# NNP-DWG-165-001-000_BP2_System_Pg_2_of_6.net
KiCad netlist of a schematic drawn in Altium Designer
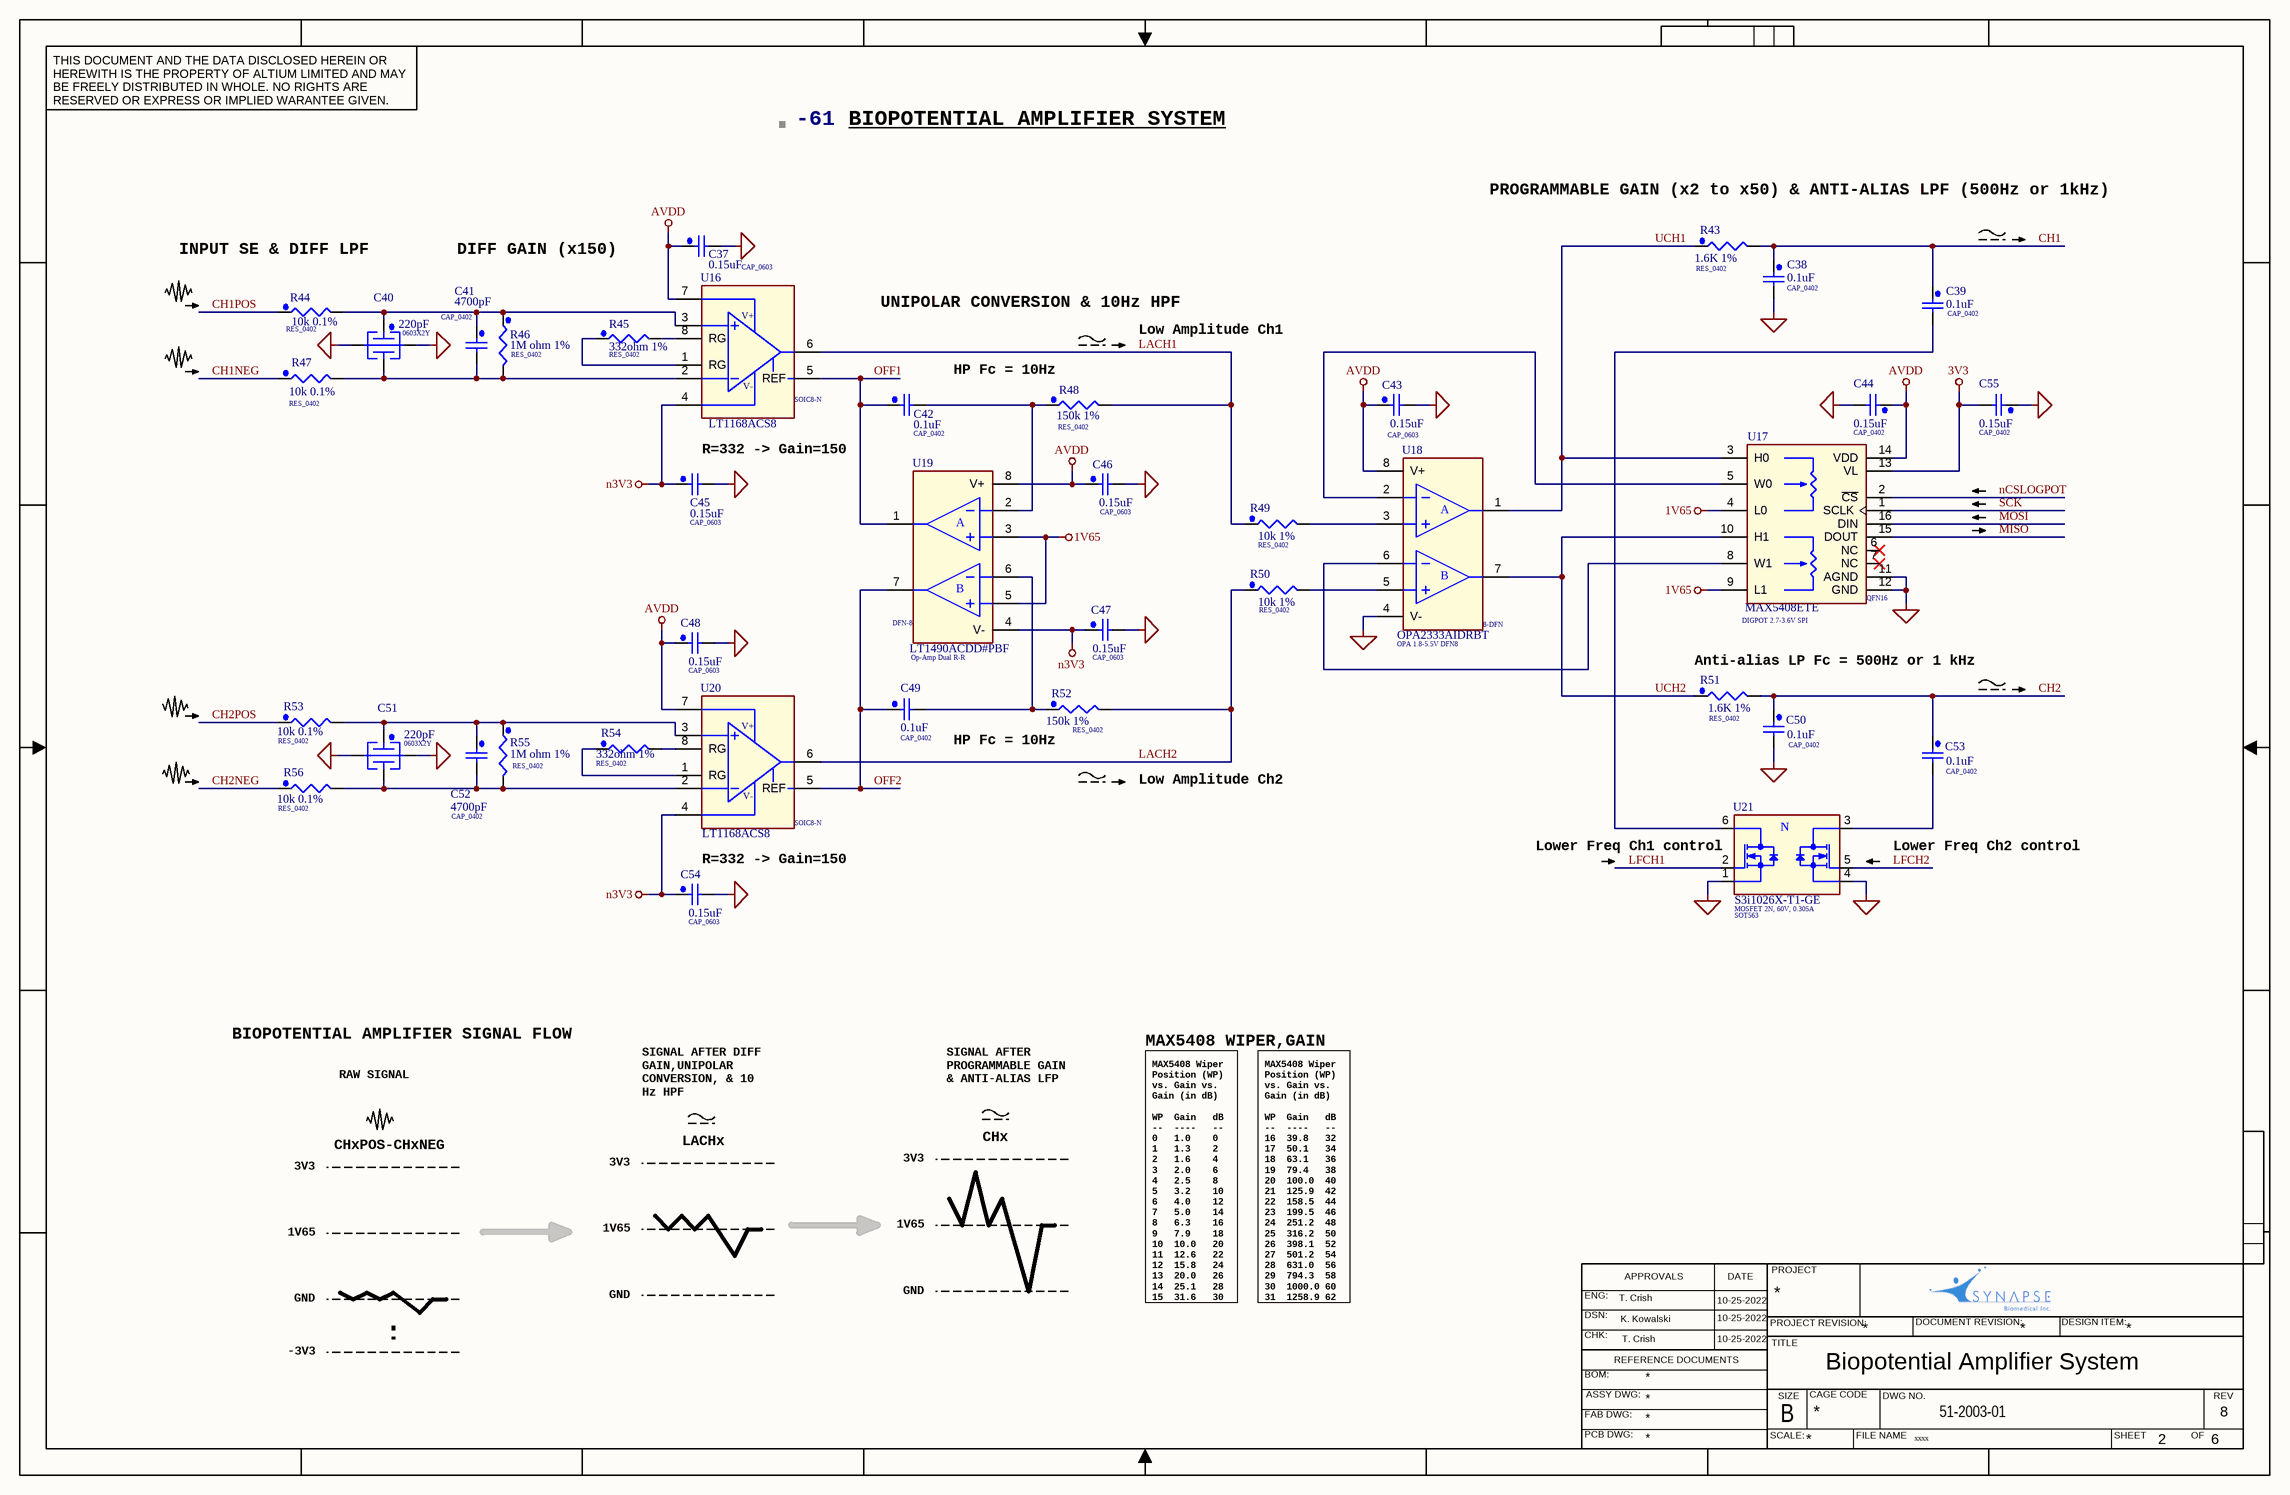
[diagram p0: NNP-DWG-165-001-000 BP2 System Pg 2 of 6.SchDoc]

(export (version "E")
  (design (tool "Eeschema 10.0.6"))
  (components
    (comp (ref "-61")
      (value "BOM_S1")
      (description "BOM item small graphic")
      (fields (field (name "XDESCRIPTION") "BIOPOTENTIAL AMPLIFIER SYSTEM"))
      (libsource (lib "BOM_sym") (part "BOM_S1"))
    )
    (comp (ref "C37")
      (value "0.15uF")
      (footprint "CAP_0603")
      (description "0.15uF, 16V, X7R, 10%, 0603, RoHS")
      (fields
        (field (name "MFR") "Samsung Corp")
        (field (name "PACKAGEDESCRIPTION") "CAP_0603")
        (field (name "MPN") "CL05B154KO5NNNC")
      )
      (libsource (lib "NNPS Integrated Parts") (part "GRM188R71C154KA01D"))
    )
    (comp (ref "C38")
      (value "0.1uF")
      (footprint "CAP_0402")
      (description "0.1uF, 16V, X7R, 0402, RoHS")
      (fields
        (field (name "MFR") "Murata Electronics North America")
        (field (name "PACKAGEDESCRIPTION") "CAP_0402")
        (field (name "MPN") "GRM155R71C104KA88D")
      )
      (libsource (lib "NNPS Integrated Parts") (part "GRM155R71C104KA88D"))
    )
    (comp (ref "C39")
      (value "0.1uF")
      (footprint "CAP_0402")
      (description "0.1uF, 16V, X7R, 0402, RoHS")
      (fields
        (field (name "MFR") "Murata Electronics North America")
        (field (name "PACKAGEDESCRIPTION") "CAP_0402")
        (field (name "MPN") "GRM155R71C104KA88D")
      )
      (libsource (lib "NNPS Integrated Parts") (part "GRM155R71C104KA88D"))
    )
    (comp (ref "C40")
      (value "220pF")
      (footprint "CAP_0603_X14")
      (description "X2Y, 220pF, 50V, X7R, 0603, 20%, RoHS")
      (fields
        (field (name "MFR") "Johanson Dielectrics Inc")
        (field (name "PACKAGEDESCRIPTION") "0603X2Y")
        (field (name "MPN") "500X14W221MV4T")
      )
      (libsource (lib "NNPS Integrated Parts") (part "500X14W103MV4T"))
    )
    (comp (ref "C41")
      (value "4700pF")
      (footprint "CAP_0402")
      (description "4700pF, 50V, C0G, 0402_10%, RoHS")
      (fields
        (field (name "MFR") "Murata Electronics North America")
        (field (name "PACKAGEDESCRIPTION") "CAP_0402")
        (field (name "MPN") "GRM155R71H472KA01D")
      )
      (libsource (lib "NNPS Integrated Parts") (part "C0402C472K5RACTU"))
    )
    (comp (ref "C42")
      (value "0.1uF")
      (footprint "CAP_0402")
      (description "0.1uF, 16V, X7R, 0402, RoHS")
      (fields
        (field (name "MFR") "Murata Electronics North America")
        (field (name "PACKAGEDESCRIPTION") "CAP_0402")
        (field (name "MPN") "GRM155R71C104KA88D")
      )
      (libsource (lib "NNPS Integrated Parts") (part "GRM155R71C104KA88D"))
    )
    (comp (ref "C43")
      (value "0.15uF")
      (footprint "CAP_0603")
      (description "0.15uF, 16V, X7R, 10%, 0603, RoHS")
      (fields
        (field (name "MFR") "Samsung Corp")
        (field (name "PACKAGEDESCRIPTION") "CAP_0603")
        (field (name "MPN") "CL05B154KO5NNNC")
      )
      (libsource (lib "NNPS Integrated Parts") (part "GRM188R71C154KA01D"))
    )
    (comp (ref "C44")
      (value "0.15uF")
      (footprint "CAP_0402")
      (description "0.15uF, 16V, X7R, 10%, 0402, RoHS")
      (fields
        (field (name "MFR") "Murata Electronics North America")
        (field (name "PACKAGEDESCRIPTION") "CAP_0402")
        (field (name "MPN") "GRM155R71C154KA12D")
      )
      (libsource (lib "altium-import") (part "root_2_GRM188R71C154KA01D_"))
    )
    (comp (ref "C45")
      (value "0.15uF")
      (footprint "CAP_0603")
      (description "0.15uF, 16V, X7R, 10%, 0603, RoHS")
      (fields
        (field (name "MFR") "Samsung Corp")
        (field (name "PACKAGEDESCRIPTION") "CAP_0603")
        (field (name "MPN") "CL05B154KO5NNNC")
      )
      (libsource (lib "NNPS Integrated Parts") (part "GRM188R71C154KA01D"))
    )
    (comp (ref "C46")
      (value "0.15uF")
      (footprint "CAP_0603")
      (description "0.15uF, 16V, X7R, 10%, 0603, RoHS")
      (fields
        (field (name "MFR") "Samsung Corp")
        (field (name "PACKAGEDESCRIPTION") "CAP_0603")
        (field (name "MPN") "CL05B154KO5NNNC")
      )
      (libsource (lib "NNPS Integrated Parts") (part "GRM188R71C154KA01D"))
    )
    (comp (ref "C47")
      (value "0.15uF")
      (footprint "CAP_0603")
      (description "0.15uF, 16V, X7R, 10%, 0603, RoHS")
      (fields
        (field (name "MFR") "Samsung Corp")
        (field (name "PACKAGEDESCRIPTION") "CAP_0603")
        (field (name "MPN") "CL05B154KO5NNNC")
      )
      (libsource (lib "NNPS Integrated Parts") (part "GRM188R71C154KA01D"))
    )
    (comp (ref "C48")
      (value "0.15uF")
      (footprint "CAP_0603")
      (description "0.15uF, 16V, X7R, 10%, 0603, RoHS")
      (fields
        (field (name "MFR") "Samsung Corp")
        (field (name "PACKAGEDESCRIPTION") "CAP_0603")
        (field (name "MPN") "CL05B154KO5NNNC")
      )
      (libsource (lib "NNPS Integrated Parts") (part "GRM188R71C154KA01D"))
    )
    (comp (ref "C49")
      (value "0.1uF")
      (footprint "CAP_0402")
      (description "0.1uF, 16V, X7R, 0402, RoHS")
      (fields
        (field (name "MFR") "Murata Electronics North America")
        (field (name "PACKAGEDESCRIPTION") "CAP_0402")
        (field (name "MPN") "GRM155R71C104KA88D")
      )
      (libsource (lib "NNPS Integrated Parts") (part "GRM155R71C104KA88D"))
    )
    (comp (ref "C50")
      (value "0.1uF")
      (footprint "CAP_0402")
      (description "0.1uF, 16V, X7R, 0402, RoHS")
      (fields
        (field (name "MFR") "Murata Electronics North America")
        (field (name "PACKAGEDESCRIPTION") "CAP_0402")
        (field (name "MPN") "GRM155R71C104KA88D")
      )
      (libsource (lib "NNPS Integrated Parts") (part "GRM155R71C104KA88D"))
    )
    (comp (ref "C51")
      (value "220pF")
      (footprint "CAP_0603_X14")
      (description "X2Y, 220pF, 50V, X7R, 0603, 20%, RoHS")
      (fields
        (field (name "MFR") "Johanson Dielectrics Inc")
        (field (name "PACKAGEDESCRIPTION") "0603X2Y")
        (field (name "MPN") "500X14W221MV4T")
      )
      (libsource (lib "NNPS Integrated Parts") (part "500X14W103MV4T"))
    )
    (comp (ref "C52")
      (value "4700pF")
      (footprint "CAP_0402")
      (description "4700pF, 50V, C0G, 0402_10%, RoHS")
      (fields
        (field (name "MFR") "Murata Electronics North America")
        (field (name "PACKAGEDESCRIPTION") "CAP_0402")
        (field (name "MPN") "GRM155R71H472KA01D")
      )
      (libsource (lib "NNPS Integrated Parts") (part "C0402C472K5RACTU"))
    )
    (comp (ref "C53")
      (value "0.1uF")
      (footprint "CAP_0402")
      (description "0.1uF, 16V, X7R, 0402, RoHS")
      (fields
        (field (name "MFR") "Murata Electronics North America")
        (field (name "PACKAGEDESCRIPTION") "CAP_0402")
        (field (name "MPN") "GRM155R71C104KA88D")
      )
      (libsource (lib "NNPS Integrated Parts") (part "GRM155R71C104KA88D"))
    )
    (comp (ref "C54")
      (value "0.15uF")
      (footprint "CAP_0603")
      (description "0.15uF, 16V, X7R, 10%, 0603, RoHS")
      (fields
        (field (name "MFR") "Samsung Corp")
        (field (name "PACKAGEDESCRIPTION") "CAP_0603")
        (field (name "MPN") "CL05B154KO5NNNC")
      )
      (libsource (lib "NNPS Integrated Parts") (part "GRM188R71C154KA01D"))
    )
    (comp (ref "C55")
      (value "0.15uF")
      (footprint "CAP_0402")
      (description "0.15uF, 16V, X7R, 10%, 0402, RoHS")
      (fields
        (field (name "MFR") "Murata Electronics North America")
        (field (name "PACKAGEDESCRIPTION") "CAP_0402")
        (field (name "MPN") "GRM155R71C154KA12D")
      )
      (libsource (lib "altium-import") (part "root_2_GRM188R71C154KA01D_"))
    )
    (comp (ref "R43")
      (value "1.6K 1%")
      (footprint "RES_0402")
      (description "1.6K ohm, 1%, 1/16W, smd, 0402, RoHS")
      (fields
        (field (name "MFR") "Vishay Dale")
        (field (name "PACKAGEDESCRIPTION") "RES_0402")
        (field (name "MPN") "CRCW04021K60FKED")
      )
      (libsource (lib "NNPS Integrated Parts") (part "CRCW04021K60FKED"))
    )
    (comp (ref "R44")
      (value "10k 0.1%")
      (footprint "RES_0402")
      (description "10k ohm, 0.1%, 1/16W, 0402, RoHS")
      (fields
        (field (name "MFR") "Vishay Dale")
        (field (name "PACKAGEDESCRIPTION") "RES_0402")
        (field (name "MPN") "TNPW040210K0BEED")
      )
      (libsource (lib "NNPS Integrated Parts") (part "TNPW040210K0BEED"))
    )
    (comp (ref "R45")
      (value "332ohm 1%")
      (footprint "RES_0402")
      (description "332 ohm, 1%, 1/16W, 0402, RoHS")
      (fields
        (field (name "MFR") "Vishay Dale")
        (field (name "PACKAGEDESCRIPTION") "RES_0402")
        (field (name "MPN") "CRCW0402332RFKED")
      )
      (libsource (lib "NNPS Integrated Parts") (part "CRCW0402332RFKED"))
    )
    (comp (ref "R46")
      (value "1M ohm 1%")
      (footprint "RES_0402")
      (description "1M ohm, 1%, 1/16W, 0402, RoHS")
      (fields
        (field (name "MFR") "Vishay Dale")
        (field (name "PACKAGEDESCRIPTION") "RES_0402")
        (field (name "MPN") "CRCW04021M00FKED")
      )
      (libsource (lib "NNPS Integrated Parts") (part "CRCW04021M00FKED"))
    )
    (comp (ref "R47")
      (value "10k 0.1%")
      (footprint "RES_0402")
      (description "10k ohm, 0.1%, 1/16W, 0402, RoHS")
      (fields
        (field (name "MFR") "Vishay Dale")
        (field (name "PACKAGEDESCRIPTION") "RES_0402")
        (field (name "MPN") "TNPW040210K0BEED")
      )
      (libsource (lib "NNPS Integrated Parts") (part "TNPW040210K0BEED"))
    )
    (comp (ref "R48")
      (value "150k 1%")
      (footprint "RES_0402")
      (description "150k ohm, 1%, 1/16W, smd, 0402, RoHS")
      (fields
        (field (name "MFR") "Vishay Dale")
        (field (name "PACKAGEDESCRIPTION") "RES_0402")
        (field (name "MPN") "CRCW0402150KFKED")
      )
      (libsource (lib "NNPS Integrated Parts") (part "CRCW0402150KFKED"))
    )
    (comp (ref "R49")
      (value "10k 1%")
      (footprint "RES_0402")
      (description "10.0k ohm, 1%, 1/16W, smd, 0402, RoHS")
      (fields
        (field (name "MFR") "Vishay Dale")
        (field (name "PACKAGEDESCRIPTION") "RES_0402")
        (field (name "MPN") "CRCW040210K0FKED")
      )
      (libsource (lib "NNPS Integrated Parts") (part "MCR01MZPF1002"))
    )
    (comp (ref "R50")
      (value "10k 1%")
      (footprint "RES_0402")
      (description "10.0k ohm, 1%, 1/16W, smd, 0402, RoHS")
      (fields
        (field (name "MFR") "Vishay Dale")
        (field (name "PACKAGEDESCRIPTION") "RES_0402")
        (field (name "MPN") "CRCW040210K0FKED")
      )
      (libsource (lib "NNPS Integrated Parts") (part "MCR01MZPF1002"))
    )
    (comp (ref "R51")
      (value "1.6K 1%")
      (footprint "RES_0402")
      (description "1.6K ohm, 1%, 1/16W, smd, 0402, RoHS")
      (fields
        (field (name "MFR") "Vishay Dale")
        (field (name "PACKAGEDESCRIPTION") "RES_0402")
        (field (name "MPN") "CRCW04021K60FKED")
      )
      (libsource (lib "NNPS Integrated Parts") (part "CRCW04021K60FKED"))
    )
    (comp (ref "R52")
      (value "150k 1%")
      (footprint "RES_0402")
      (description "150k ohm, 1%, 1/16W, smd, 0402, RoHS")
      (fields
        (field (name "MFR") "Vishay Dale")
        (field (name "PACKAGEDESCRIPTION") "RES_0402")
        (field (name "MPN") "CRCW0402150KFKED")
      )
      (libsource (lib "NNPS Integrated Parts") (part "CRCW0402150KFKED"))
    )
    (comp (ref "R53")
      (value "10k 0.1%")
      (footprint "RES_0402")
      (description "10k ohm, 0.1%, 1/16W, 0402, RoHS")
      (fields
        (field (name "MFR") "Vishay Dale")
        (field (name "PACKAGEDESCRIPTION") "RES_0402")
        (field (name "MPN") "TNPW040210K0BEED")
      )
      (libsource (lib "NNPS Integrated Parts") (part "TNPW040210K0BEED"))
    )
    (comp (ref "R54")
      (value "332ohm 1%")
      (footprint "RES_0402")
      (description "332 ohm, 1%, 1/16W, 0402, RoHS")
      (fields
        (field (name "MFR") "Vishay Dale")
        (field (name "PACKAGEDESCRIPTION") "RES_0402")
        (field (name "MPN") "CRCW0402332RFKED")
      )
      (libsource (lib "NNPS Integrated Parts") (part "CRCW0402332RFKED"))
    )
    (comp (ref "R55")
      (value "1M ohm 1%")
      (footprint "RES_0402")
      (description "1M ohm, 1%, 1/16W, 0402, RoHS")
      (fields
        (field (name "MFR") "Vishay Dale")
        (field (name "PACKAGEDESCRIPTION") "RES_0402")
        (field (name "MPN") "CRCW04021M00FKED")
      )
      (libsource (lib "NNPS Integrated Parts") (part "CRCW04021M00FKED"))
    )
    (comp (ref "R56")
      (value "10k 0.1%")
      (footprint "RES_0402")
      (description "10k ohm, 0.1%, 1/16W, 0402, RoHS")
      (fields
        (field (name "MFR") "Vishay Dale")
        (field (name "PACKAGEDESCRIPTION") "RES_0402")
        (field (name "MPN") "TNPW040210K0BEED")
      )
      (libsource (lib "NNPS Integrated Parts") (part "TNPW040210K0BEED"))
    )
    (comp (ref "U16")
      (value "INA 2.3-18V 530uA")
      (footprint "SOIC8-N")
      (description "Op-Amp Instrumentation, 400kHz, SOIC8-N, RoHS")
      (fields
        (field (name "MFR") "Linear Technology")
        (field (name "PACKAGEDESCRIPTION") "SOIC8-N")
        (field (name "MPN") "LT1168ACS8")
      )
      (libsource (lib "NNPS Integrated Parts") (part "LT1168ACS8"))
    )
    (comp (ref "U17")
      (value "DIGPOT 2.7-3.6V SPI")
      (footprint "QFN16")
      (description "Digipot, 2.7-3.6V,  SPI, QFN16, RoHS")
      (fields
        (field (name "MFR") "Maxim")
        (field (name "PACKAGEDESCRIPTION") "QFN16")
        (field (name "MPN") "MAX5408ETE")
      )
      (libsource (lib "NNPS Integrated Parts") (part "MAX5408ETE"))
    )
    (comp (ref "U18")
      (value "OPA 1.8-5.5V DFN8")
      (footprint "TI-DRB8-2400X1650TP_V")
      (description "OPA, 1.8-5.5V, DFN8, RoHS")
      (fields
        (field (name "PACKAGEDESCRIPTION") "8-DFN")
        (field (name "MFR") "Texas Instruments")
        (field (name "MPN") "OPA2333AIDRBT")
      )
      (libsource (lib "NNPS Integrated Parts") (part "OPA2333AIDRBT"))
    )
    (comp (ref "U19")
      (value "Op-Amp Dual R-R")
      (footprint "DFN8")
      (description "Op-Amp, Dual, R-R, DFN8, RoHS")
      (fields
        (field (name "PACKAGEDESCRIPTION") "DFN-8")
        (field (name "MFR") "Linear Technology")
        (field (name "MPN") "LT1490ACDD#PBF")
      )
      (libsource (lib "NNPS Integrated Parts") (part "LT1490ACDD"))
    )
    (comp (ref "U20")
      (value "INA 2.3-18V 530uA")
      (footprint "SOIC8-N")
      (description "Op-Amp Instrumentation, 400kHz, SOIC8-N, RoHS")
      (fields
        (field (name "MFR") "Linear Technology")
        (field (name "PACKAGEDESCRIPTION") "SOIC8-N")
        (field (name "MPN") "LT1168ACS8")
      )
      (libsource (lib "NNPS Integrated Parts") (part "LT1168ACS8"))
    )
    (comp (ref "U21")
      (value "MOSFET 2N, 60V, 0.305A")
      (footprint "SOT-563")
      (description "MOSFET 2N, 60V, 0.305A, RoHS")
      (fields
        (field (name "MFR") "Vishay")
        (field (name "PACKAGEDESCRIPTION") "SOT563")
        (field (name "MPN") "S3i1026X-T1-GE")
      )
      (libsource (lib "NNPS Integrated Parts") (part "Si1026X-T1-E3"))
    )
  )
  (nets
    (net (code "1") (name "/CH1") (class "Default")
      (node (ref "C38") (pin "1") (pinfunction "1_1") (pintype "passive"))
      (node (ref "C39") (pin "1") (pinfunction "1_1") (pintype "passive"))
      (node (ref "R43") (pin "2") (pinfunction "2_2") (pintype "passive"))
    )
    (net (code "2") (name "/CH1NEG") (class "Default")
      (node (ref "R47") (pin "1") (pinfunction "1_1") (pintype "passive"))
    )
    (net (code "3") (name "/CH1POS") (class "Default")
      (node (ref "R44") (pin "1") (pinfunction "1_1") (pintype "passive"))
    )
    (net (code "4") (name "/CH2") (class "Default")
      (node (ref "C50") (pin "1") (pinfunction "1_1") (pintype "passive"))
      (node (ref "C53") (pin "1") (pinfunction "1_1") (pintype "passive"))
      (node (ref "R51") (pin "2") (pinfunction "2_2") (pintype "passive"))
    )
    (net (code "5") (name "/CH2NEG") (class "Default")
      (node (ref "R56") (pin "1") (pinfunction "1_1") (pintype "passive"))
    )
    (net (code "6") (name "/CH2POS") (class "Default")
      (node (ref "R53") (pin "1") (pinfunction "1_1") (pintype "passive"))
    )
    (net (code "7") (name "/LACH1") (class "Default")
      (node (ref "R48") (pin "2") (pinfunction "2_2") (pintype "passive"))
      (node (ref "R49") (pin "1") (pinfunction "1_1") (pintype "passive"))
      (node (ref "U16") (pin "6") (pinfunction "OUT_6") (pintype "passive"))
    )
    (net (code "8") (name "/LACH2") (class "Default")
      (node (ref "R50") (pin "1") (pinfunction "1_1") (pintype "passive"))
      (node (ref "R52") (pin "2") (pinfunction "2_2") (pintype "passive"))
      (node (ref "U20") (pin "6") (pinfunction "OUT_6") (pintype "passive"))
    )
    (net (code "9") (name "/LFCH1") (class "Default")
      (node (ref "U21") (pin "2") (pinfunction "G1_2") (pintype "passive"))
    )
    (net (code "10") (name "/LFCH2") (class "Default")
      (node (ref "U21") (pin "5") (pinfunction "G2_5") (pintype "passive"))
    )
    (net (code "11") (name "/MISO") (class "Default")
      (node (ref "U17") (pin "15") (pinfunction "DOUT_15") (pintype "passive"))
    )
    (net (code "12") (name "/MOSI") (class "Default")
      (node (ref "U17") (pin "16") (pinfunction "DIN_16") (pintype "passive"))
    )
    (net (code "13") (name "/OFF1") (class "Default")
      (node (ref "C42") (pin "1") (pinfunction "1_1") (pintype "passive"))
      (node (ref "U16") (pin "5") (pinfunction "REF_5") (pintype "passive"))
      (node (ref "U19") (pin "1") (pinfunction "OUT_A_1") (pintype "passive"))
    )
    (net (code "14") (name "/OFF2") (class "Default")
      (node (ref "C49") (pin "1") (pinfunction "1_1") (pintype "passive"))
      (node (ref "U19") (pin "7") (pinfunction "OUT_B_7") (pintype "passive"))
      (node (ref "U20") (pin "5") (pinfunction "REF_5") (pintype "passive"))
    )
    (net (code "15") (name "/SCK") (class "Default")
      (node (ref "U17") (pin "1") (pinfunction "SCLK_1") (pintype "passive"))
    )
    (net (code "16") (name "/UCH1") (class "Default")
      (node (ref "R43") (pin "1") (pinfunction "1_1") (pintype "passive"))
      (node (ref "U17") (pin "3") (pinfunction "H0_3") (pintype "passive"))
      (node (ref "U18") (pin "1") (pinfunction "OUT_A_1") (pintype "passive"))
    )
    (net (code "17") (name "/UCH2") (class "Default")
      (node (ref "R51") (pin "1") (pinfunction "1_1") (pintype "passive"))
      (node (ref "U17") (pin "10") (pinfunction "H1_10") (pintype "passive"))
      (node (ref "U18") (pin "7") (pinfunction "OUT_B_7") (pintype "passive"))
    )
    (net (code "18") (name "/nCSLOGPOT") (class "Default")
      (node (ref "U17") (pin "2") (pinfunction "CS_2") (pintype "passive"))
    )
    (net (code "19") (name "1V65") (class "Default")
      (node (ref "U17") (pin "4") (pinfunction "L0_4") (pintype "passive"))
      (node (ref "U17") (pin "9") (pinfunction "L1_9") (pintype "passive"))
      (node (ref "U19") (pin "3") (pinfunction "+IN_A_3") (pintype "passive"))
      (node (ref "U19") (pin "5") (pinfunction "+IN_B_5") (pintype "passive"))
    )
    (net (code "20") (name "3V3") (class "Default")
      (node (ref "C55") (pin "2") (pinfunction "2_2") (pintype "passive"))
      (node (ref "U17") (pin "13") (pinfunction "VL_13") (pintype "passive"))
    )
    (net (code "21") (name "AVDD") (class "Default")
      (node (ref "C37") (pin "1") (pinfunction "1_1") (pintype "passive"))
      (node (ref "C43") (pin "1") (pinfunction "1_1") (pintype "passive"))
      (node (ref "C44") (pin "1") (pinfunction "1_1") (pintype "passive"))
      (node (ref "C46") (pin "1") (pinfunction "1_1") (pintype "passive"))
      (node (ref "C48") (pin "1") (pinfunction "1_1") (pintype "passive"))
      (node (ref "U16") (pin "7") (pinfunction "+VS_7") (pintype "passive"))
      (node (ref "U17") (pin "14") (pinfunction "VDD_14") (pintype "passive"))
      (node (ref "U18") (pin "8") (pinfunction "V+_8") (pintype "passive"))
      (node (ref "U19") (pin "8") (pinfunction "V+_8") (pintype "passive"))
      (node (ref "U20") (pin "7") (pinfunction "+VS_7") (pintype "passive"))
    )
    (net (code "22") (name "GND") (class "Default")
      (node (ref "C37") (pin "2") (pinfunction "2_2") (pintype "passive"))
      (node (ref "C38") (pin "2") (pinfunction "2_2") (pintype "passive"))
      (node (ref "C40") (pin "3") (pinfunction "G1_3") (pintype "passive"))
      (node (ref "C40") (pin "4") (pinfunction "G2_4") (pintype "passive"))
      (node (ref "C43") (pin "2") (pinfunction "2_2") (pintype "passive"))
      (node (ref "C44") (pin "2") (pinfunction "2_2") (pintype "passive"))
      (node (ref "C45") (pin "2") (pinfunction "2_2") (pintype "passive"))
      (node (ref "C46") (pin "2") (pinfunction "2_2") (pintype "passive"))
      (node (ref "C47") (pin "2") (pinfunction "2_2") (pintype "passive"))
      (node (ref "C48") (pin "2") (pinfunction "2_2") (pintype "passive"))
      (node (ref "C50") (pin "2") (pinfunction "2_2") (pintype "passive"))
      (node (ref "C51") (pin "3") (pinfunction "G1_3") (pintype "passive"))
      (node (ref "C51") (pin "4") (pinfunction "G2_4") (pintype "passive"))
      (node (ref "C54") (pin "2") (pinfunction "2_2") (pintype "passive"))
      (node (ref "C55") (pin "1") (pinfunction "1_1") (pintype "passive"))
      (node (ref "U17") (pin "11") (pinfunction "AGND_11") (pintype "passive"))
      (node (ref "U17") (pin "12") (pinfunction "GND_12") (pintype "passive"))
      (node (ref "U18") (pin "4") (pinfunction "V-_4") (pintype "passive"))
      (node (ref "U21") (pin "1") (pinfunction "S1_1") (pintype "passive"))
      (node (ref "U21") (pin "4") (pinfunction "S2_4") (pintype "passive"))
    )
    (net (code "23") (name "Net-(C40-A)") (class "Default")
      (node (ref "C40") (pin "1") (pinfunction "A_1") (pintype "passive"))
      (node (ref "C41") (pin "1") (pinfunction "1_1") (pintype "passive"))
      (node (ref "R44") (pin "2") (pinfunction "2_2") (pintype "passive"))
      (node (ref "R46") (pin "1") (pinfunction "1_1") (pintype "passive"))
      (node (ref "U16") (pin "3") (pinfunction "+IN_3") (pintype "passive"))
    )
    (net (code "24") (name "Net-(C40-B)") (class "Default")
      (node (ref "C40") (pin "2") (pinfunction "B_2") (pintype "passive"))
      (node (ref "C41") (pin "2") (pinfunction "2_2") (pintype "passive"))
      (node (ref "R46") (pin "2") (pinfunction "2_2") (pintype "passive"))
      (node (ref "R47") (pin "2") (pinfunction "2_2") (pintype "passive"))
      (node (ref "U16") (pin "2") (pinfunction "-IN_2") (pintype "passive"))
    )
    (net (code "25") (name "Net-(C51-A)") (class "Default")
      (node (ref "C51") (pin "1") (pinfunction "A_1") (pintype "passive"))
      (node (ref "C52") (pin "1") (pinfunction "1_1") (pintype "passive"))
      (node (ref "R53") (pin "2") (pinfunction "2_2") (pintype "passive"))
      (node (ref "R55") (pin "1") (pinfunction "1_1") (pintype "passive"))
      (node (ref "U20") (pin "3") (pinfunction "+IN_3") (pintype "passive"))
    )
    (net (code "26") (name "Net-(C51-B)") (class "Default")
      (node (ref "C51") (pin "2") (pinfunction "B_2") (pintype "passive"))
      (node (ref "C52") (pin "2") (pinfunction "2_2") (pintype "passive"))
      (node (ref "R55") (pin "2") (pinfunction "2_2") (pintype "passive"))
      (node (ref "R56") (pin "2") (pinfunction "2_2") (pintype "passive"))
      (node (ref "U20") (pin "2") (pinfunction "-IN_2") (pintype "passive"))
    )
    (net (code "27") (name "Net-(R45-Pad1)") (class "Default")
      (node (ref "R45") (pin "1") (pinfunction "1_1") (pintype "passive"))
      (node (ref "U16") (pin "1") (pinfunction "RG_1") (pintype "passive"))
    )
    (net (code "28") (name "Net-(R45-Pad2)") (class "Default")
      (node (ref "R45") (pin "2") (pinfunction "2_2") (pintype "passive"))
      (node (ref "U16") (pin "8") (pinfunction "RG_8") (pintype "passive"))
    )
    (net (code "29") (name "Net-(R54-Pad1)") (class "Default")
      (node (ref "R54") (pin "1") (pinfunction "1_1") (pintype "passive"))
      (node (ref "U20") (pin "1") (pinfunction "RG_1") (pintype "passive"))
    )
    (net (code "30") (name "Net-(R54-Pad2)") (class "Default")
      (node (ref "R54") (pin "2") (pinfunction "2_2") (pintype "passive"))
      (node (ref "U20") (pin "8") (pinfunction "RG_8") (pintype "passive"))
    )
    (net (code "31") (name "Net-(U17-W0)") (class "Default")
      (node (ref "U17") (pin "5") (pinfunction "W0_5") (pintype "passive"))
      (node (ref "U18") (pin "2") (pinfunction "-IN_A_2") (pintype "passive"))
    )
    (net (code "32") (name "Net-(U17-W1)") (class "Default")
      (node (ref "U17") (pin "8") (pinfunction "W1_8") (pintype "passive"))
      (node (ref "U18") (pin "6") (pinfunction "-IN_B_6") (pintype "passive"))
    )
    (net (code "33") (name "Net-(U18-+IN_A)") (class "Default")
      (node (ref "R49") (pin "2") (pinfunction "2_2") (pintype "passive"))
      (node (ref "U18") (pin "3") (pinfunction "+IN_A_3") (pintype "passive"))
    )
    (net (code "34") (name "Net-(U18-+IN_B)") (class "Default")
      (node (ref "R50") (pin "2") (pinfunction "2_2") (pintype "passive"))
      (node (ref "U18") (pin "5") (pinfunction "+IN_B_5") (pintype "passive"))
    )
    (net (code "35") (name "Net-(U19--IN_A)") (class "Default")
      (node (ref "C42") (pin "2") (pinfunction "2_2") (pintype "passive"))
      (node (ref "R48") (pin "1") (pinfunction "1_1") (pintype "passive"))
      (node (ref "U19") (pin "2") (pinfunction "-IN_A_2") (pintype "passive"))
    )
    (net (code "36") (name "Net-(U19--IN_B)") (class "Default")
      (node (ref "C49") (pin "2") (pinfunction "2_2") (pintype "passive"))
      (node (ref "R52") (pin "1") (pinfunction "1_1") (pintype "passive"))
      (node (ref "U19") (pin "6") (pinfunction "-IN_B_6") (pintype "passive"))
    )
    (net (code "37") (name "Net-(U21-D1)") (class "Default")
      (node (ref "C39") (pin "2") (pinfunction "2_2") (pintype "passive"))
      (node (ref "U21") (pin "6") (pinfunction "D1_6") (pintype "passive"))
    )
    (net (code "38") (name "Net-(U21-D2)") (class "Default")
      (node (ref "C53") (pin "2") (pinfunction "2_2") (pintype "passive"))
      (node (ref "U21") (pin "3") (pinfunction "D2_3") (pintype "passive"))
    )
    (net (code "39") (name "n3V3") (class "Default")
      (node (ref "C45") (pin "1") (pinfunction "1_1") (pintype "passive"))
      (node (ref "C47") (pin "1") (pinfunction "1_1") (pintype "passive"))
      (node (ref "C54") (pin "1") (pinfunction "1_1") (pintype "passive"))
      (node (ref "U16") (pin "4") (pinfunction "-VS_4") (pintype "passive"))
      (node (ref "U19") (pin "4") (pinfunction "V-_4") (pintype "passive"))
      (node (ref "U20") (pin "4") (pinfunction "-VS_4") (pintype "passive"))
    )
    (net (code "40") (name "unconnected-(U17-NC-Pad6)") (class "Default")
      (node (ref "U17") (pin "6") (pinfunction "NC_6") (pintype "passive+no_connect"))
    )
    (net (code "41") (name "unconnected-(U17-NC-Pad7)") (class "Default")
      (node (ref "U17") (pin "7") (pinfunction "NC_7") (pintype "passive+no_connect"))
    )
  )
)
